# Gate_Driver.net
KiCad netlist of a schematic drawn in Altium Designer
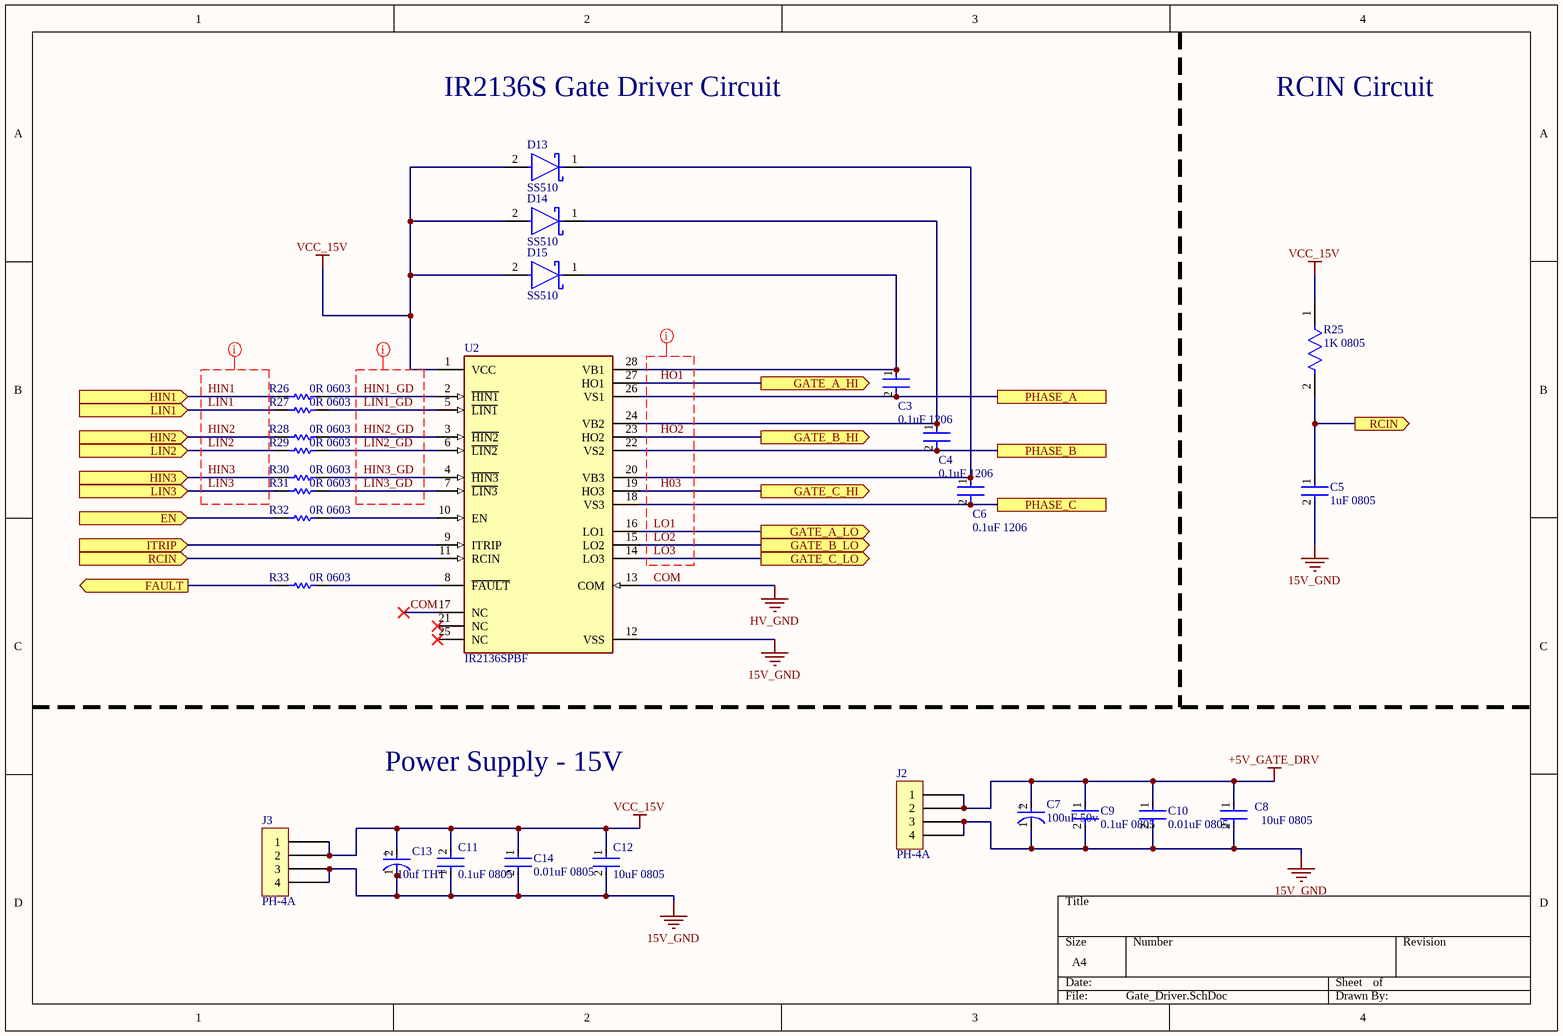
[diagram p0: Gate_Driver.SchDoc]

(export (version "E")
  (design (tool "Eeschema 10.0.6"))
  (components
    (comp (ref "C3")
      (value "0.1uF 1206")
      (footprint "C1206")
      (description "0.1uF/100nF 50V Capacitor ±10% Tolerance CC1206KRX7R9BB104 – 1206 Package")
      (libsource (lib "1kW_BLDC_Controller") (part "0.1uF 1206"))
    )
    (comp (ref "C4")
      (value "0.1uF 1206")
      (footprint "C1206")
      (description "0.1uF/100nF 50V Capacitor ±10% Tolerance CC1206KRX7R9BB104 – 1206 Package")
      (libsource (lib "1kW_BLDC_Controller") (part "0.1uF 1206"))
    )
    (comp (ref "C5")
      (value "1uF 0805")
      (footprint "R0805")
      (description "1uF/1000nF 50V Capacitor ±10% Tolerance CC0805KKX7R9BB105 – 0805 Package")
      (libsource (lib "1kW_BLDC_Controller") (part "1uF 0805"))
    )
    (comp (ref "C6")
      (value "0.1uF 1206")
      (footprint "C1206")
      (description "0.1uF/100nF 50V Capacitor ±10% Tolerance CC1206KRX7R9BB104 – 1206 Package")
      (libsource (lib "1kW_BLDC_Controller") (part "0.1uF 1206"))
    )
    (comp (ref "C7")
      (value "100uF 50v")
      (footprint "FP-EEU-FR1H101B-MFG")
      (description "100uF 50V Electrolytic Capacitor – JWCO")
      (fields (field (name "TOLERANCE") "20%"))
      (libsource (lib "Altium Content Vault") (part "cf48714ba7e38822c1575c7ec0b6d1f"))
    )
    (comp (ref "C8")
      (value "10uF 0805")
      (footprint "R0805")
      (description "10uF/1000nF 50V Capacitor ±10% Tolerance CC0805KKX5R9BB106 – 0805 Package")
      (libsource (lib "1kW_BLDC_Controller") (part "10uF 0805"))
    )
    (comp (ref "C9")
      (value "0.1uF 0805")
      (footprint "R0805")
      (description "0.1uF/100nF 100V Capacitor ±10% Tolerance CC0805KKX7R0BB104 – 0805 Package")
      (libsource (lib "1kW_BLDC_Controller") (part "0.1uF 0805"))
    )
    (comp (ref "C10")
      (value "0.01uF 0805")
      (footprint "R0805")
      (description "10nF/0.01uF 50V Capacitor ±10% Tolerance 0805B103K500CT – 0805 Package")
      (libsource (lib "1kW_BLDC_Controller") (part "0.01uF 0805"))
    )
    (comp (ref "C11")
      (value "0.1uF 0805")
      (footprint "R0805")
      (description "0.1uF/100nF 100V Capacitor ±10% Tolerance CC0805KKX7R0BB104 – 0805 Package")
      (libsource (lib "1kW_BLDC_Controller") (part "0.1uF 0805"))
    )
    (comp (ref "C12")
      (value "10uF 0805")
      (footprint "R0805")
      (description "10uF/1000nF 50V Capacitor ±10% Tolerance CC0805KKX5R9BB106 – 0805 Package")
      (libsource (lib "1kW_BLDC_Controller") (part "10uF 0805"))
    )
    (comp (ref "C13")
      (value "10uf THT")
      (footprint "FP-RAD-TH-D_10_0_5-L_20_2-MFG")
      (description "Aluminum Electrolytic Capacitors (Radial Lead Type) 10uF ±20% 350V")
      (fields (field (name "TOLERANCE") "20%"))
      (libsource (lib "Altium Content Vault") (part "203bc49f2ac43e59fd269a8c329ed05"))
    )
    (comp (ref "C14")
      (value "0.01uF 0805")
      (footprint "R0805")
      (description "10nF/0.01uF 50V Capacitor ±10% Tolerance 0805B103K500CT – 0805 Package")
      (libsource (lib "1kW_BLDC_Controller") (part "0.01uF 0805"))
    )
    (comp (ref "D13")
      (value "SS510")
      (footprint "DO-210AA")
      (description "SS510-E3/52T – 100V 5A High Voltage Schottky Diode – DO-214AA Package")
      (libsource (lib "1kW_BLDC_Controller") (part "SS510"))
    )
    (comp (ref "D14")
      (value "SS510")
      (footprint "DO-210AA")
      (description "SS510-E3/52T – 100V 5A High Voltage Schottky Diode – DO-214AA Package")
      (libsource (lib "1kW_BLDC_Controller") (part "SS510"))
    )
    (comp (ref "D15")
      (value "SS510")
      (footprint "DO-210AA")
      (description "SS510-E3/52T – 100V 5A High Voltage Schottky Diode – DO-214AA Package")
      (libsource (lib "1kW_BLDC_Controller") (part "SS510"))
    )
    (comp (ref "J2")
      (value "PH-4A")
      (footprint "JST PH-4A")
      (description "4 Pin JST PH-4A Straight Male Connector – 2mm Pitch")
      (libsource (lib "1kW_BLDC_Controller") (part "4 Pin JST PH-4A"))
    )
    (comp (ref "J3")
      (value "PH-4A")
      (footprint "JST PH-4A")
      (description "4 Pin JST PH-4A Straight Male Connector – 2mm Pitch")
      (libsource (lib "1kW_BLDC_Controller") (part "4 Pin JST PH-4A"))
    )
    (comp (ref "R25")
      (value "1K 0805")
      (footprint "R0805")
      (description "1K Ohm 1/8 Watt Resistor 1% Tolerance 0805S8F1001T5E – 0805 Package")
      (libsource (lib "1kW_BLDC_Controller") (part "1k 0805"))
    )
    (comp (ref "R26")
      (value "0R 0603")
      (footprint "R0603")
      (description "0 Ohm 1/10 Watt Resistor 1% Tolerance RC0603FR-070RL – 0603 Package")
      (libsource (lib "1kW_BLDC_Controller") (part "R0000 0603"))
    )
    (comp (ref "R27")
      (value "0R 0603")
      (footprint "R0603")
      (description "0 Ohm 1/10 Watt Resistor 1% Tolerance RC0603FR-070RL – 0603 Package")
      (libsource (lib "1kW_BLDC_Controller") (part "R0000 0603"))
    )
    (comp (ref "R28")
      (value "0R 0603")
      (footprint "R0603")
      (description "0 Ohm 1/10 Watt Resistor 1% Tolerance RC0603FR-070RL – 0603 Package")
      (libsource (lib "1kW_BLDC_Controller") (part "R0000 0603"))
    )
    (comp (ref "R29")
      (value "0R 0603")
      (footprint "R0603")
      (description "0 Ohm 1/10 Watt Resistor 1% Tolerance RC0603FR-070RL – 0603 Package")
      (libsource (lib "1kW_BLDC_Controller") (part "R0000 0603"))
    )
    (comp (ref "R30")
      (value "0R 0603")
      (footprint "R0603")
      (description "0 Ohm 1/10 Watt Resistor 1% Tolerance RC0603FR-070RL – 0603 Package")
      (libsource (lib "1kW_BLDC_Controller") (part "R0000 0603"))
    )
    (comp (ref "R31")
      (value "0R 0603")
      (footprint "R0603")
      (description "0 Ohm 1/10 Watt Resistor 1% Tolerance RC0603FR-070RL – 0603 Package")
      (libsource (lib "1kW_BLDC_Controller") (part "R0000 0603"))
    )
    (comp (ref "R32")
      (value "0R 0603")
      (footprint "R0603")
      (description "0 Ohm 1/10 Watt Resistor 1% Tolerance RC0603FR-070RL – 0603 Package")
      (libsource (lib "1kW_BLDC_Controller") (part "R0000 0603"))
    )
    (comp (ref "R33")
      (value "0R 0603")
      (footprint "R0603")
      (description "0 Ohm 1/10 Watt Resistor 1% Tolerance RC0603FR-070RL – 0603 Package")
      (libsource (lib "1kW_BLDC_Controller") (part "R0000 0603"))
    )
    (comp (ref "U2")
      (value "IR2136SPBF")
      (footprint "FP-PG-DSO-28-IPC_C")
      (description "IC GATE DRVR HALF-BRIDGE 28SOIC")
      (libsource (lib "Altium Content Vault") (part "8b2c3bafb3edbd55fb91afaa445bd66"))
    )
  )
  (nets
    (net (code "1") (name "+5V_GATE_DRV") (class "Default")
      (node (ref "C10") (pin "1") (pinfunction "1_1") (pintype "passive"))
      (node (ref "C7") (pin "2") (pinfunction "A_2") (pintype "passive"))
      (node (ref "C8") (pin "1") (pinfunction "1_1") (pintype "passive"))
      (node (ref "C9") (pin "1") (pinfunction "1_1") (pintype "passive"))
      (node (ref "J2") (pin "1") (pinfunction "1_1") (pintype "passive"))
      (node (ref "J2") (pin "2") (pinfunction "2_2") (pintype "passive"))
    )
    (net (code "2") (name "/EN") (class "Default")
      (node (ref "R32") (pin "1") (pinfunction "1_1") (pintype "passive"))
    )
    (net (code "3") (name "/FAULT") (class "Default")
      (node (ref "R33") (pin "1") (pinfunction "1_1") (pintype "passive"))
    )
    (net (code "4") (name "/H03") (class "Default")
      (node (ref "U2") (pin "19") (pinfunction "HO3_19") (pintype "passive"))
    )
    (net (code "5") (name "/HIN1") (class "Default")
      (node (ref "R26") (pin "1") (pinfunction "1_1") (pintype "passive"))
    )
    (net (code "6") (name "/HIN1_GD") (class "Default")
      (node (ref "R26") (pin "2") (pinfunction "2_2") (pintype "passive"))
      (node (ref "U2") (pin "2") (pinfunction "~{HIN1}_2") (pintype "input"))
    )
    (net (code "7") (name "/HIN2") (class "Default")
      (node (ref "R28") (pin "1") (pinfunction "1_1") (pintype "passive"))
    )
    (net (code "8") (name "/HIN2_GD") (class "Default")
      (node (ref "R28") (pin "2") (pinfunction "2_2") (pintype "passive"))
      (node (ref "U2") (pin "3") (pinfunction "~{HIN2}_3") (pintype "input"))
    )
    (net (code "9") (name "/HIN3") (class "Default")
      (node (ref "R30") (pin "1") (pinfunction "1_1") (pintype "passive"))
    )
    (net (code "10") (name "/HIN3_GD") (class "Default")
      (node (ref "R30") (pin "2") (pinfunction "2_2") (pintype "passive"))
      (node (ref "U2") (pin "4") (pinfunction "~{HIN3}_4") (pintype "input"))
    )
    (net (code "11") (name "/HO1") (class "Default")
      (node (ref "U2") (pin "27") (pinfunction "HO1_27") (pintype "passive"))
    )
    (net (code "12") (name "/HO2") (class "Default")
      (node (ref "U2") (pin "23") (pinfunction "HO2_23") (pintype "passive"))
    )
    (net (code "13") (name "/ITRIP") (class "Default")
      (node (ref "U2") (pin "9") (pinfunction "ITRIP_9") (pintype "input"))
    )
    (net (code "14") (name "/LIN1") (class "Default")
      (node (ref "R27") (pin "1") (pinfunction "1_1") (pintype "passive"))
    )
    (net (code "15") (name "/LIN1_GD") (class "Default")
      (node (ref "R27") (pin "2") (pinfunction "2_2") (pintype "passive"))
      (node (ref "U2") (pin "5") (pinfunction "~{LIN1}_5") (pintype "input"))
    )
    (net (code "16") (name "/LIN2") (class "Default")
      (node (ref "R29") (pin "1") (pinfunction "1_1") (pintype "passive"))
    )
    (net (code "17") (name "/LIN2_GD") (class "Default")
      (node (ref "R29") (pin "2") (pinfunction "2_2") (pintype "passive"))
      (node (ref "U2") (pin "6") (pinfunction "~{LIN2}_6") (pintype "input"))
    )
    (net (code "18") (name "/LIN3") (class "Default")
      (node (ref "R31") (pin "1") (pinfunction "1_1") (pintype "passive"))
    )
    (net (code "19") (name "/LIN3_GD") (class "Default")
      (node (ref "R31") (pin "2") (pinfunction "2_2") (pintype "passive"))
      (node (ref "U2") (pin "7") (pinfunction "~{LIN3}_7") (pintype "input"))
    )
    (net (code "20") (name "/LO1") (class "Default")
      (node (ref "U2") (pin "16") (pinfunction "LO1_16") (pintype "passive"))
    )
    (net (code "21") (name "/LO2") (class "Default")
      (node (ref "U2") (pin "15") (pinfunction "LO2_15") (pintype "passive"))
    )
    (net (code "22") (name "/LO3") (class "Default")
      (node (ref "U2") (pin "14") (pinfunction "LO3_14") (pintype "passive"))
    )
    (net (code "23") (name "/PHASE_A") (class "Default")
      (node (ref "C3") (pin "2") (pinfunction "2_2") (pintype "passive"))
      (node (ref "U2") (pin "26") (pinfunction "VS1_26") (pintype "power_in"))
    )
    (net (code "24") (name "/PHASE_B") (class "Default")
      (node (ref "C4") (pin "2") (pinfunction "2_2") (pintype "passive"))
      (node (ref "U2") (pin "22") (pinfunction "VS2_22") (pintype "power_in"))
    )
    (net (code "25") (name "/PHASE_C") (class "Default")
      (node (ref "C6") (pin "2") (pinfunction "2_2") (pintype "passive"))
      (node (ref "U2") (pin "18") (pinfunction "VS3_18") (pintype "power_in"))
    )
    (net (code "26") (name "/RCIN") (class "Default")
      (node (ref "C5") (pin "1") (pinfunction "1_1") (pintype "passive"))
      (node (ref "R25") (pin "2") (pinfunction "2_2") (pintype "passive"))
      (node (ref "U2") (pin "11") (pinfunction "RCIN_11") (pintype "input"))
    )
    (net (code "27") (name "15V_GND") (class "Default")
      (node (ref "C10") (pin "2") (pinfunction "2_2") (pintype "passive"))
      (node (ref "C11") (pin "1") (pinfunction "1_1") (pintype "passive"))
      (node (ref "C12") (pin "2") (pinfunction "2_2") (pintype "passive"))
      (node (ref "C13") (pin "1") (pinfunction "C_1") (pintype "passive"))
      (node (ref "C14") (pin "2") (pinfunction "2_2") (pintype "passive"))
      (node (ref "C5") (pin "2") (pinfunction "2_2") (pintype "passive"))
      (node (ref "C7") (pin "1") (pinfunction "C_1") (pintype "passive"))
      (node (ref "C8") (pin "2") (pinfunction "2_2") (pintype "passive"))
      (node (ref "C9") (pin "2") (pinfunction "2_2") (pintype "passive"))
      (node (ref "J2") (pin "3") (pinfunction "3_3") (pintype "passive"))
      (node (ref "J2") (pin "4") (pinfunction "4_4") (pintype "passive"))
      (node (ref "J3") (pin "3") (pinfunction "3_3") (pintype "passive"))
      (node (ref "J3") (pin "4") (pinfunction "4_4") (pintype "passive"))
      (node (ref "U2") (pin "12") (pinfunction "VSS_12") (pintype "power_in"))
    )
    (net (code "28") (name "HV_GND") (class "Default")
      (node (ref "U2") (pin "13") (pinfunction "COM_13") (pintype "input"))
      (node (ref "U2") (pin "17") (pinfunction "NC_17") (pintype "passive"))
    )
    (net (code "29") (name "Net-(D13-C)") (class "Default")
      (node (ref "C6") (pin "1") (pinfunction "1_1") (pintype "passive"))
      (node (ref "D13") (pin "1") (pinfunction "C_1") (pintype "passive"))
      (node (ref "U2") (pin "20") (pinfunction "VB3_20") (pintype "power_in"))
    )
    (net (code "30") (name "Net-(D14-C)") (class "Default")
      (node (ref "C4") (pin "1") (pinfunction "1_1") (pintype "passive"))
      (node (ref "D14") (pin "1") (pinfunction "C_1") (pintype "passive"))
      (node (ref "U2") (pin "24") (pinfunction "VB2_24") (pintype "power_in"))
    )
    (net (code "31") (name "Net-(D15-C)") (class "Default")
      (node (ref "C3") (pin "1") (pinfunction "1_1") (pintype "passive"))
      (node (ref "D15") (pin "1") (pinfunction "C_1") (pintype "passive"))
      (node (ref "U2") (pin "28") (pinfunction "VB1_28") (pintype "power_in"))
    )
    (net (code "32") (name "Net-(U2-EN)") (class "Default")
      (node (ref "R32") (pin "2") (pinfunction "2_2") (pintype "passive"))
      (node (ref "U2") (pin "10") (pinfunction "EN_10") (pintype "input"))
    )
    (net (code "33") (name "Net-(U2-~{FAULT})") (class "Default")
      (node (ref "R33") (pin "2") (pinfunction "2_2") (pintype "passive"))
      (node (ref "U2") (pin "8") (pinfunction "~{FAULT}_8") (pintype "open_collector"))
    )
    (net (code "34") (name "VCC_15V") (class "Default")
      (node (ref "C11") (pin "2") (pinfunction "2_2") (pintype "passive"))
      (node (ref "C12") (pin "1") (pinfunction "1_1") (pintype "passive"))
      (node (ref "C13") (pin "2") (pinfunction "A_2") (pintype "passive"))
      (node (ref "C14") (pin "1") (pinfunction "1_1") (pintype "passive"))
      (node (ref "D13") (pin "2") (pinfunction "A_2") (pintype "passive"))
      (node (ref "D14") (pin "2") (pinfunction "A_2") (pintype "passive"))
      (node (ref "D15") (pin "2") (pinfunction "A_2") (pintype "passive"))
      (node (ref "J3") (pin "1") (pinfunction "1_1") (pintype "passive"))
      (node (ref "J3") (pin "2") (pinfunction "2_2") (pintype "passive"))
      (node (ref "R25") (pin "1") (pinfunction "1_1") (pintype "passive"))
      (node (ref "U2") (pin "1") (pinfunction "VCC_1") (pintype "power_in"))
    )
    (net (code "35") (name "unconnected-(U2-NC-Pad21)") (class "Default")
      (node (ref "U2") (pin "21") (pinfunction "NC_21") (pintype "passive+no_connect"))
    )
    (net (code "36") (name "unconnected-(U2-NC-Pad25)") (class "Default")
      (node (ref "U2") (pin "25") (pinfunction "NC_25") (pintype "passive+no_connect"))
    )
  )
)
